# Nixie_Clock_ESP32_IN14.net
KiCad netlist of a schematic drawn in EAGLE
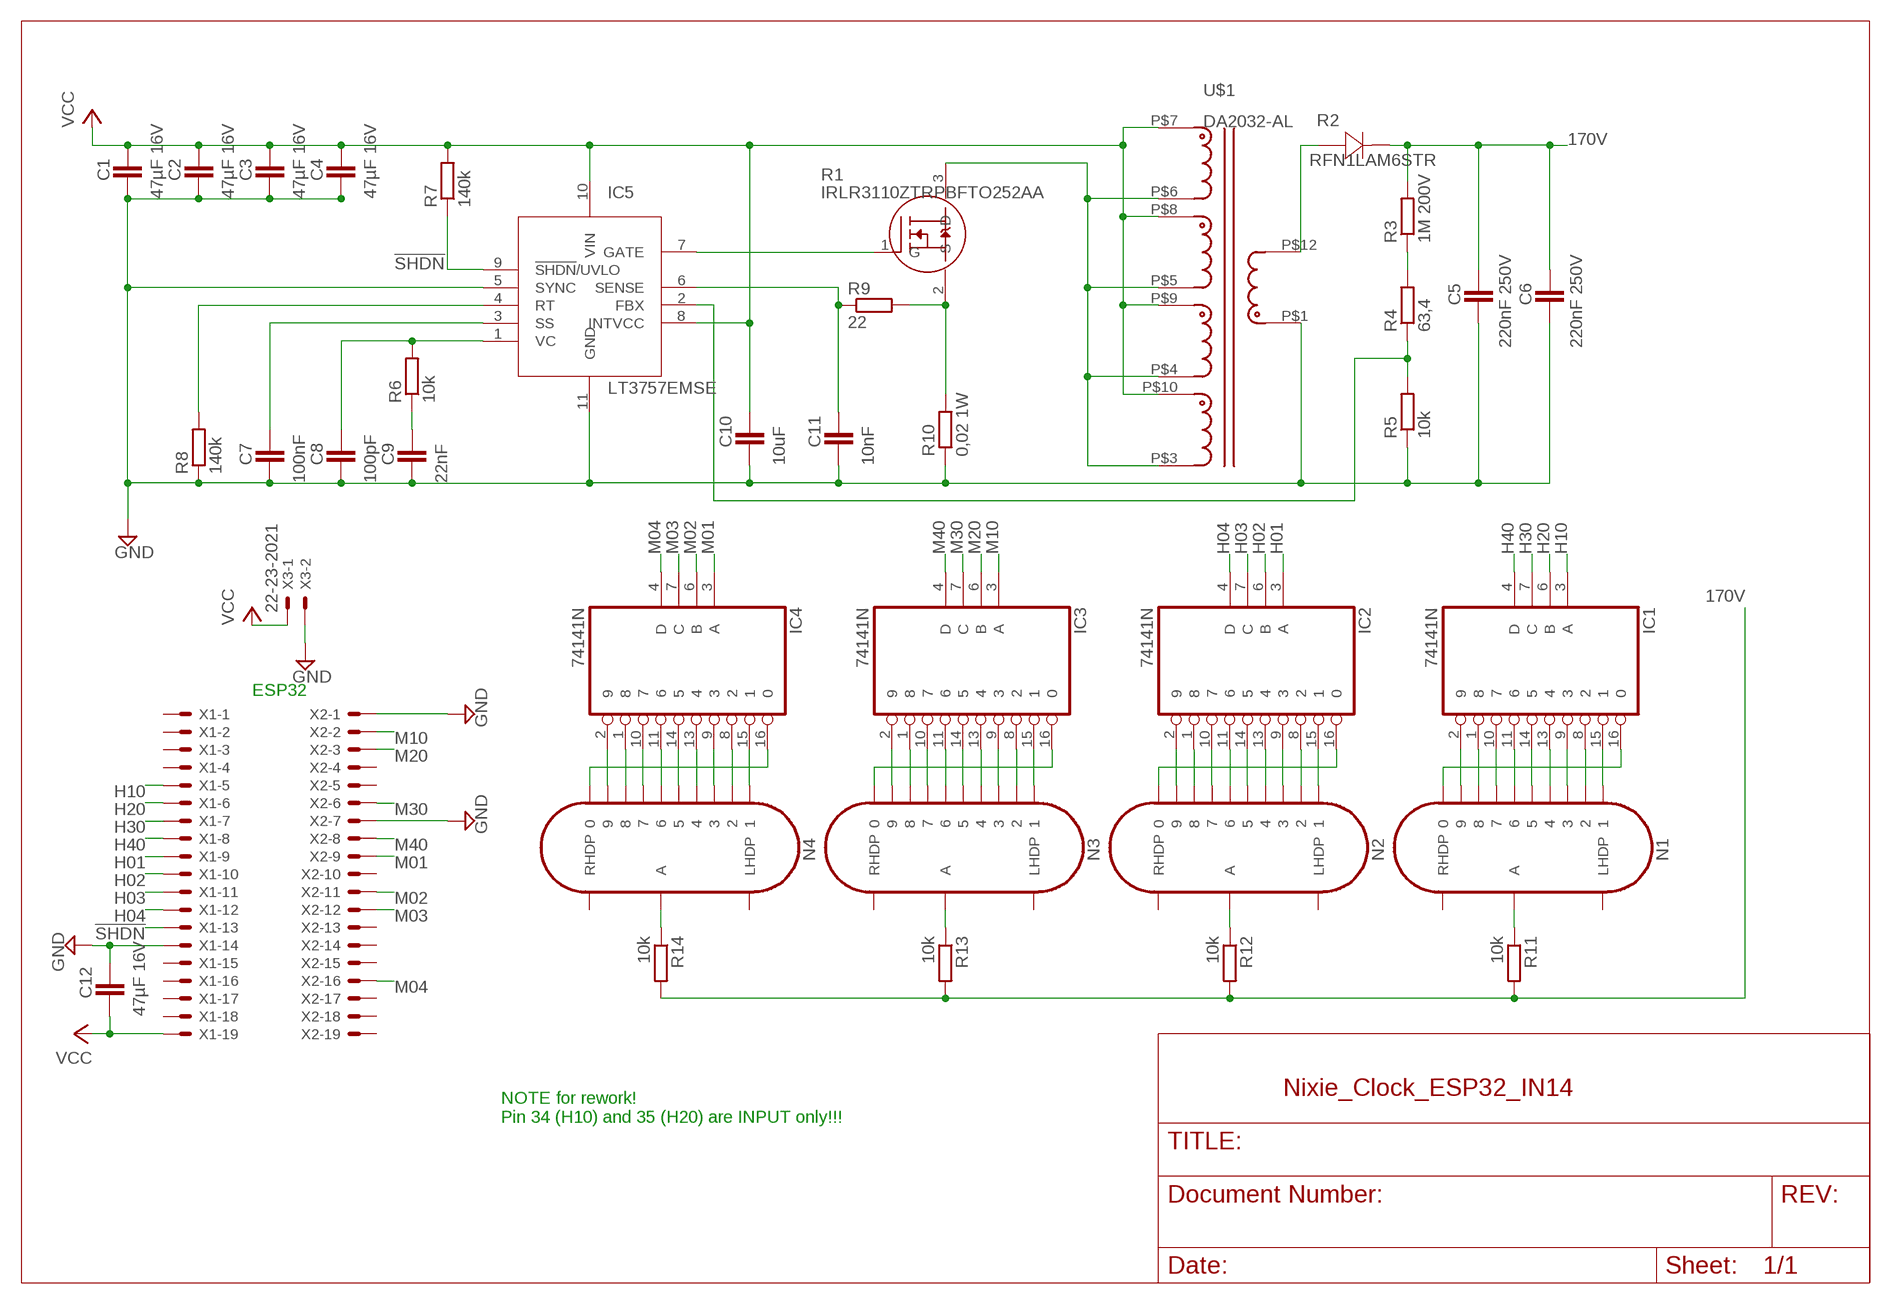
[diagram p0: schematic, sheet 1]

(export (version "E")
  (design (tool "Eeschema 10.0.6"))
  (components
    (comp (ref "C1")
      (value "47µF 16V")
      (footprint "eagle-import:C1210")
      (libsource (lib "eagle-import") (part "C-EUC1210"))
    )
    (comp (ref "C2")
      (value "47µF 16V")
      (footprint "eagle-import:C1210")
      (libsource (lib "eagle-import") (part "C-EUC1210"))
    )
    (comp (ref "C3")
      (value "47µF 16V")
      (footprint "eagle-import:C1210")
      (libsource (lib "eagle-import") (part "C-EUC1210"))
    )
    (comp (ref "C4")
      (value "47µF 16V")
      (footprint "eagle-import:C1210")
      (libsource (lib "eagle-import") (part "C-EUC1210"))
    )
    (comp (ref "C5")
      (value "220nF 250V")
      (footprint "eagle-import:C1206")
      (libsource (lib "eagle-import") (part "C-EUC1206"))
    )
    (comp (ref "C6")
      (value "220nF 250V")
      (footprint "eagle-import:C1206")
      (libsource (lib "eagle-import") (part "C-EUC1206"))
    )
    (comp (ref "C7")
      (value "100nF")
      (footprint "eagle-import:C0805")
      (libsource (lib "eagle-import") (part "C-EUC0805"))
    )
    (comp (ref "C8")
      (value "100pF")
      (footprint "eagle-import:C0805")
      (libsource (lib "eagle-import") (part "C-EUC0805"))
    )
    (comp (ref "C9")
      (value "22nF")
      (footprint "eagle-import:C0805")
      (libsource (lib "eagle-import") (part "C-EUC0805"))
    )
    (comp (ref "C10")
      (value "10uF")
      (footprint "eagle-import:C0805")
      (libsource (lib "eagle-import") (part "C-EUC0805"))
    )
    (comp (ref "C11")
      (value "10nF")
      (footprint "eagle-import:C0805")
      (libsource (lib "eagle-import") (part "C-EUC0805"))
    )
    (comp (ref "C12")
      (value "47µF 16V")
      (footprint "eagle-import:C1210")
      (libsource (lib "eagle-import") (part "C-EUC1210"))
    )
    (comp (ref "IC1")
      (value "74141N")
      (footprint "eagle-import:DIL16")
      (libsource (lib "eagle-import") (part "74141N"))
    )
    (comp (ref "IC2")
      (value "74141N")
      (footprint "eagle-import:DIL16")
      (libsource (lib "eagle-import") (part "74141N"))
    )
    (comp (ref "IC3")
      (value "74141N")
      (footprint "eagle-import:DIL16")
      (libsource (lib "eagle-import") (part "74141N"))
    )
    (comp (ref "IC4")
      (value "74141N")
      (footprint "eagle-import:DIL16")
      (libsource (lib "eagle-import") (part "74141N"))
    )
    (comp (ref "IC5")
      (value "LT3757EMSE")
      (footprint "eagle-import:MSOP10")
      (libsource (lib "eagle-import") (part "LT3757EMSE"))
    )
    (comp (ref "N1")
      (value "IN-14")
      (footprint "eagle-import:IN-14")
      (libsource (lib "eagle-import") (part "IN-14"))
    )
    (comp (ref "N2")
      (value "IN-14")
      (footprint "eagle-import:IN-14")
      (libsource (lib "eagle-import") (part "IN-14"))
    )
    (comp (ref "N3")
      (value "IN-14")
      (footprint "eagle-import:IN-14")
      (libsource (lib "eagle-import") (part "IN-14"))
    )
    (comp (ref "N4")
      (value "IN-14")
      (footprint "eagle-import:IN-14")
      (libsource (lib "eagle-import") (part "IN-14"))
    )
    (comp (ref "R1")
      (value "IRLR3110ZTRPBFTO252AA")
      (footprint "eagle-import:TO252")
      (libsource (lib "eagle-import") (part "IRLR3110ZTRPBFTO252AA"))
    )
    (comp (ref "R2")
      (value "RFN1LAM6STR")
      (footprint "eagle-import:DIO_RB050LAM_ROM")
      (fields (field (name "COPYRIGHT") "Copyright (C) 2018 Accelerated Designs. All rights reserved"))
      (libsource (lib "eagle-import") (part "RFN1LAM6STR"))
    )
    (comp (ref "R3")
      (value "1M 200V")
      (footprint "eagle-import:R0805")
      (libsource (lib "eagle-import") (part "R-EU_R0805"))
    )
    (comp (ref "R4")
      (value "63,4")
      (footprint "eagle-import:R0805")
      (libsource (lib "eagle-import") (part "R-EU_R0805"))
    )
    (comp (ref "R5")
      (value "10k")
      (footprint "eagle-import:R0805")
      (libsource (lib "eagle-import") (part "R-EU_R0805"))
    )
    (comp (ref "R6")
      (value "10k")
      (footprint "eagle-import:R0805")
      (libsource (lib "eagle-import") (part "R-EU_R0805"))
    )
    (comp (ref "R7")
      (value "140k")
      (footprint "eagle-import:R0805")
      (libsource (lib "eagle-import") (part "R-EU_R0805"))
    )
    (comp (ref "R8")
      (value "140k")
      (footprint "eagle-import:R0805")
      (libsource (lib "eagle-import") (part "R-EU_R0805"))
    )
    (comp (ref "R9")
      (value "22")
      (footprint "eagle-import:R1206")
      (libsource (lib "eagle-import") (part "R-EU_R1206"))
    )
    (comp (ref "R10")
      (value "0,02 1W")
      (footprint "eagle-import:R2010")
      (libsource (lib "eagle-import") (part "R-EU_R2010"))
    )
    (comp (ref "R11")
      (value "10k")
      (footprint "eagle-import:R0805")
      (libsource (lib "eagle-import") (part "R-EU_R0805"))
    )
    (comp (ref "R12")
      (value "10k")
      (footprint "eagle-import:R0805")
      (libsource (lib "eagle-import") (part "R-EU_R0805"))
    )
    (comp (ref "R13")
      (value "10k")
      (footprint "eagle-import:R0805")
      (libsource (lib "eagle-import") (part "R-EU_R0805"))
    )
    (comp (ref "R14")
      (value "10k")
      (footprint "eagle-import:R0805")
      (libsource (lib "eagle-import") (part "R-EU_R0805"))
    )
    (comp (ref "U$1")
      (value "DA2032-AL")
      (footprint "eagle-import:DA2032-AL")
      (libsource (lib "eagle-import") (part "DA2032-AL"))
    )
    (comp (ref "X1")
      (value "C-GRID-19-70543")
      (footprint "eagle-import:70543-19")
      (fields (field (name "MF") "MOLEX"))
      (libsource (lib "eagle-import") (part "C-GRID-19-70543"))
    )
    (comp (ref "X2")
      (value "C-GRID-19-70543")
      (footprint "eagle-import:70543-19")
      (fields (field (name "MF") "MOLEX"))
      (libsource (lib "eagle-import") (part "C-GRID-19-70543"))
    )
    (comp (ref "X3")
      (value "22-23-2021")
      (footprint "eagle-import:22-23-2021")
      (fields (field (name "MF") "MOLEX"))
      (libsource (lib "eagle-import") (part "22-23-2021"))
    )
  )
  (nets
    (net (code "1") (name "/170V") (class "Default")
      (node (ref "C5") (pin "1") (pinfunction "1_1") (pintype "passive"))
      (node (ref "C6") (pin "1") (pinfunction "1_1") (pintype "passive"))
      (node (ref "R11") (pin "2") (pinfunction "2_2") (pintype "passive"))
      (node (ref "R12") (pin "2") (pinfunction "2_2") (pintype "passive"))
      (node (ref "R13") (pin "2") (pinfunction "2_2") (pintype "passive"))
      (node (ref "R14") (pin "2") (pinfunction "2_2") (pintype "passive"))
      (node (ref "R2") (pin "1") (pinfunction "0_1") (pintype "passive"))
      (node (ref "R3") (pin "2") (pinfunction "2_2") (pintype "passive"))
    )
    (net (code "2") (name "/H01") (class "Default")
      (node (ref "IC2") (pin "3") (pinfunction "A_3") (pintype "input"))
      (node (ref "X1") (pin "9") (pinfunction "S_9") (pintype "passive"))
    )
    (net (code "3") (name "/H02") (class "Default")
      (node (ref "IC2") (pin "6") (pinfunction "B_6") (pintype "input"))
      (node (ref "X1") (pin "10") (pinfunction "S_10") (pintype "passive"))
    )
    (net (code "4") (name "/H03") (class "Default")
      (node (ref "IC2") (pin "7") (pinfunction "C_7") (pintype "input"))
      (node (ref "X1") (pin "11") (pinfunction "S_11") (pintype "passive"))
    )
    (net (code "5") (name "/H04") (class "Default")
      (node (ref "IC2") (pin "4") (pinfunction "D_4") (pintype "input"))
      (node (ref "X1") (pin "12") (pinfunction "S_12") (pintype "passive"))
    )
    (net (code "6") (name "/H10") (class "Default")
      (node (ref "IC1") (pin "3") (pinfunction "A_3") (pintype "input"))
      (node (ref "X1") (pin "5") (pinfunction "S_5") (pintype "passive"))
    )
    (net (code "7") (name "/H20") (class "Default")
      (node (ref "IC1") (pin "6") (pinfunction "B_6") (pintype "input"))
      (node (ref "X1") (pin "6") (pinfunction "S_6") (pintype "passive"))
    )
    (net (code "8") (name "/H30") (class "Default")
      (node (ref "IC1") (pin "7") (pinfunction "C_7") (pintype "input"))
      (node (ref "X1") (pin "7") (pinfunction "S_7") (pintype "passive"))
    )
    (net (code "9") (name "/H40") (class "Default")
      (node (ref "IC1") (pin "4") (pinfunction "D_4") (pintype "input"))
      (node (ref "X1") (pin "8") (pinfunction "S_8") (pintype "passive"))
    )
    (net (code "10") (name "/M01") (class "Default")
      (node (ref "IC4") (pin "3") (pinfunction "A_3") (pintype "input"))
      (node (ref "X2") (pin "9") (pinfunction "S_9") (pintype "passive"))
    )
    (net (code "11") (name "/M02") (class "Default")
      (node (ref "IC4") (pin "6") (pinfunction "B_6") (pintype "input"))
      (node (ref "X2") (pin "11") (pinfunction "S_11") (pintype "passive"))
    )
    (net (code "12") (name "/M03") (class "Default")
      (node (ref "IC4") (pin "7") (pinfunction "C_7") (pintype "input"))
      (node (ref "X2") (pin "12") (pinfunction "S_12") (pintype "passive"))
    )
    (net (code "13") (name "/M04") (class "Default")
      (node (ref "IC4") (pin "4") (pinfunction "D_4") (pintype "input"))
      (node (ref "X2") (pin "16") (pinfunction "S_16") (pintype "passive"))
    )
    (net (code "14") (name "/M10") (class "Default")
      (node (ref "IC3") (pin "3") (pinfunction "A_3") (pintype "input"))
      (node (ref "X2") (pin "2") (pinfunction "S_2") (pintype "passive"))
    )
    (net (code "15") (name "/M20") (class "Default")
      (node (ref "IC3") (pin "6") (pinfunction "B_6") (pintype "input"))
      (node (ref "X2") (pin "3") (pinfunction "S_3") (pintype "passive"))
    )
    (net (code "16") (name "/M30") (class "Default")
      (node (ref "IC3") (pin "7") (pinfunction "C_7") (pintype "input"))
      (node (ref "X2") (pin "6") (pinfunction "S_6") (pintype "passive"))
    )
    (net (code "17") (name "/M40") (class "Default")
      (node (ref "IC3") (pin "4") (pinfunction "D_4") (pintype "input"))
      (node (ref "X2") (pin "8") (pinfunction "S_8") (pintype "passive"))
    )
    (net (code "18") (name "/~{SHDN}") (class "Default")
      (node (ref "IC5") (pin "9") (pinfunction "~{SHDN}/UVLO_9") (pintype "bidirectional"))
      (node (ref "R7") (pin "1") (pinfunction "1_1") (pintype "passive"))
      (node (ref "X1") (pin "13") (pinfunction "S_13") (pintype "passive"))
    )
    (net (code "19") (name "GND") (class "Default")
      (node (ref "C1") (pin "2") (pinfunction "2_2") (pintype "passive"))
      (node (ref "C10") (pin "2") (pinfunction "2_2") (pintype "passive"))
      (node (ref "C11") (pin "2") (pinfunction "2_2") (pintype "passive"))
      (node (ref "C12") (pin "1") (pinfunction "1_1") (pintype "passive"))
      (node (ref "C2") (pin "2") (pinfunction "2_2") (pintype "passive"))
      (node (ref "C3") (pin "2") (pinfunction "2_2") (pintype "passive"))
      (node (ref "C4") (pin "2") (pinfunction "2_2") (pintype "passive"))
      (node (ref "C5") (pin "2") (pinfunction "2_2") (pintype "passive"))
      (node (ref "C6") (pin "2") (pinfunction "2_2") (pintype "passive"))
      (node (ref "C7") (pin "2") (pinfunction "2_2") (pintype "passive"))
      (node (ref "C8") (pin "2") (pinfunction "2_2") (pintype "passive"))
      (node (ref "C9") (pin "2") (pinfunction "2_2") (pintype "passive"))
      (node (ref "IC5") (pin "11") (pinfunction "GND_11") (pintype "bidirectional"))
      (node (ref "IC5") (pin "5") (pinfunction "SYNC_5") (pintype "bidirectional"))
      (node (ref "R10") (pin "1") (pinfunction "1_1") (pintype "passive"))
      (node (ref "R5") (pin "1") (pinfunction "1_1") (pintype "passive"))
      (node (ref "R8") (pin "1") (pinfunction "1_1") (pintype "passive"))
      (node (ref "U$1") (pin "P$1") (pinfunction "1_P$1") (pintype "passive"))
      (node (ref "X1") (pin "14") (pinfunction "S_14") (pintype "passive"))
      (node (ref "X2") (pin "1") (pinfunction "S_1") (pintype "passive"))
      (node (ref "X2") (pin "7") (pinfunction "S_7") (pintype "passive"))
      (node (ref "X3") (pin "2") (pinfunction "S_2") (pintype "passive"))
    )
    (net (code "20") (name "Net-(C9-Pad1)") (class "Default")
      (node (ref "C9") (pin "1") (pinfunction "1_1") (pintype "passive"))
      (node (ref "R6") (pin "1") (pinfunction "1_1") (pintype "passive"))
    )
    (net (code "21") (name "Net-(IC1A-0)") (class "Default")
      (node (ref "IC1") (pin "16") (pinfunction "0_16") (pintype "open_collector"))
      (node (ref "N1") (pin "0") (pinfunction "0_0") (pintype "bidirectional"))
    )
    (net (code "22") (name "Net-(IC1A-1)") (class "Default")
      (node (ref "IC1") (pin "15") (pinfunction "1_15") (pintype "open_collector"))
      (node (ref "N1") (pin "1") (pinfunction "1_1") (pintype "bidirectional"))
    )
    (net (code "23") (name "Net-(IC1A-2)") (class "Default")
      (node (ref "IC1") (pin "8") (pinfunction "2_8") (pintype "open_collector"))
      (node (ref "N1") (pin "2") (pinfunction "2_2") (pintype "bidirectional"))
    )
    (net (code "24") (name "Net-(IC1A-3)") (class "Default")
      (node (ref "IC1") (pin "9") (pinfunction "3_9") (pintype "open_collector"))
      (node (ref "N1") (pin "3") (pinfunction "3_3") (pintype "bidirectional"))
    )
    (net (code "25") (name "Net-(IC1A-4)") (class "Default")
      (node (ref "IC1") (pin "13") (pinfunction "4_13") (pintype "open_collector"))
      (node (ref "N1") (pin "4") (pinfunction "4_4") (pintype "bidirectional"))
    )
    (net (code "26") (name "Net-(IC1A-5)") (class "Default")
      (node (ref "IC1") (pin "14") (pinfunction "5_14") (pintype "open_collector"))
      (node (ref "N1") (pin "5") (pinfunction "5_5") (pintype "bidirectional"))
    )
    (net (code "27") (name "Net-(IC1A-6)") (class "Default")
      (node (ref "IC1") (pin "11") (pinfunction "6_11") (pintype "open_collector"))
      (node (ref "N1") (pin "6") (pinfunction "6_6") (pintype "bidirectional"))
    )
    (net (code "28") (name "Net-(IC1A-7)") (class "Default")
      (node (ref "IC1") (pin "10") (pinfunction "7_10") (pintype "open_collector"))
      (node (ref "N1") (pin "7") (pinfunction "7_7") (pintype "bidirectional"))
    )
    (net (code "29") (name "Net-(IC1A-8)") (class "Default")
      (node (ref "IC1") (pin "1") (pinfunction "8_1") (pintype "open_collector"))
      (node (ref "N1") (pin "8") (pinfunction "8_8") (pintype "bidirectional"))
    )
    (net (code "30") (name "Net-(IC1A-9)") (class "Default")
      (node (ref "IC1") (pin "2") (pinfunction "9_2") (pintype "open_collector"))
      (node (ref "N1") (pin "9") (pinfunction "9_9") (pintype "bidirectional"))
    )
    (net (code "31") (name "Net-(IC2A-0)") (class "Default")
      (node (ref "IC2") (pin "16") (pinfunction "0_16") (pintype "open_collector"))
      (node (ref "N2") (pin "0") (pinfunction "0_0") (pintype "bidirectional"))
    )
    (net (code "32") (name "Net-(IC2A-1)") (class "Default")
      (node (ref "IC2") (pin "15") (pinfunction "1_15") (pintype "open_collector"))
      (node (ref "N2") (pin "1") (pinfunction "1_1") (pintype "bidirectional"))
    )
    (net (code "33") (name "Net-(IC2A-2)") (class "Default")
      (node (ref "IC2") (pin "8") (pinfunction "2_8") (pintype "open_collector"))
      (node (ref "N2") (pin "2") (pinfunction "2_2") (pintype "bidirectional"))
    )
    (net (code "34") (name "Net-(IC2A-3)") (class "Default")
      (node (ref "IC2") (pin "9") (pinfunction "3_9") (pintype "open_collector"))
      (node (ref "N2") (pin "3") (pinfunction "3_3") (pintype "bidirectional"))
    )
    (net (code "35") (name "Net-(IC2A-4)") (class "Default")
      (node (ref "IC2") (pin "13") (pinfunction "4_13") (pintype "open_collector"))
      (node (ref "N2") (pin "4") (pinfunction "4_4") (pintype "bidirectional"))
    )
    (net (code "36") (name "Net-(IC2A-5)") (class "Default")
      (node (ref "IC2") (pin "14") (pinfunction "5_14") (pintype "open_collector"))
      (node (ref "N2") (pin "5") (pinfunction "5_5") (pintype "bidirectional"))
    )
    (net (code "37") (name "Net-(IC2A-6)") (class "Default")
      (node (ref "IC2") (pin "11") (pinfunction "6_11") (pintype "open_collector"))
      (node (ref "N2") (pin "6") (pinfunction "6_6") (pintype "bidirectional"))
    )
    (net (code "38") (name "Net-(IC2A-7)") (class "Default")
      (node (ref "IC2") (pin "10") (pinfunction "7_10") (pintype "open_collector"))
      (node (ref "N2") (pin "7") (pinfunction "7_7") (pintype "bidirectional"))
    )
    (net (code "39") (name "Net-(IC2A-8)") (class "Default")
      (node (ref "IC2") (pin "1") (pinfunction "8_1") (pintype "open_collector"))
      (node (ref "N2") (pin "8") (pinfunction "8_8") (pintype "bidirectional"))
    )
    (net (code "40") (name "Net-(IC2A-9)") (class "Default")
      (node (ref "IC2") (pin "2") (pinfunction "9_2") (pintype "open_collector"))
      (node (ref "N2") (pin "9") (pinfunction "9_9") (pintype "bidirectional"))
    )
    (net (code "41") (name "Net-(IC3A-0)") (class "Default")
      (node (ref "IC3") (pin "16") (pinfunction "0_16") (pintype "open_collector"))
      (node (ref "N3") (pin "0") (pinfunction "0_0") (pintype "bidirectional"))
    )
    (net (code "42") (name "Net-(IC3A-1)") (class "Default")
      (node (ref "IC3") (pin "15") (pinfunction "1_15") (pintype "open_collector"))
      (node (ref "N3") (pin "1") (pinfunction "1_1") (pintype "bidirectional"))
    )
    (net (code "43") (name "Net-(IC3A-2)") (class "Default")
      (node (ref "IC3") (pin "8") (pinfunction "2_8") (pintype "open_collector"))
      (node (ref "N3") (pin "2") (pinfunction "2_2") (pintype "bidirectional"))
    )
    (net (code "44") (name "Net-(IC3A-3)") (class "Default")
      (node (ref "IC3") (pin "9") (pinfunction "3_9") (pintype "open_collector"))
      (node (ref "N3") (pin "3") (pinfunction "3_3") (pintype "bidirectional"))
    )
    (net (code "45") (name "Net-(IC3A-4)") (class "Default")
      (node (ref "IC3") (pin "13") (pinfunction "4_13") (pintype "open_collector"))
      (node (ref "N3") (pin "4") (pinfunction "4_4") (pintype "bidirectional"))
    )
    (net (code "46") (name "Net-(IC3A-5)") (class "Default")
      (node (ref "IC3") (pin "14") (pinfunction "5_14") (pintype "open_collector"))
      (node (ref "N3") (pin "5") (pinfunction "5_5") (pintype "bidirectional"))
    )
    (net (code "47") (name "Net-(IC3A-6)") (class "Default")
      (node (ref "IC3") (pin "11") (pinfunction "6_11") (pintype "open_collector"))
      (node (ref "N3") (pin "6") (pinfunction "6_6") (pintype "bidirectional"))
    )
    (net (code "48") (name "Net-(IC3A-7)") (class "Default")
      (node (ref "IC3") (pin "10") (pinfunction "7_10") (pintype "open_collector"))
      (node (ref "N3") (pin "7") (pinfunction "7_7") (pintype "bidirectional"))
    )
    (net (code "49") (name "Net-(IC3A-8)") (class "Default")
      (node (ref "IC3") (pin "1") (pinfunction "8_1") (pintype "open_collector"))
      (node (ref "N3") (pin "8") (pinfunction "8_8") (pintype "bidirectional"))
    )
    (net (code "50") (name "Net-(IC3A-9)") (class "Default")
      (node (ref "IC3") (pin "2") (pinfunction "9_2") (pintype "open_collector"))
      (node (ref "N3") (pin "9") (pinfunction "9_9") (pintype "bidirectional"))
    )
    (net (code "51") (name "Net-(IC4A-0)") (class "Default")
      (node (ref "IC4") (pin "16") (pinfunction "0_16") (pintype "open_collector"))
      (node (ref "N4") (pin "0") (pinfunction "0_0") (pintype "bidirectional"))
    )
    (net (code "52") (name "Net-(IC4A-1)") (class "Default")
      (node (ref "IC4") (pin "15") (pinfunction "1_15") (pintype "open_collector"))
      (node (ref "N4") (pin "1") (pinfunction "1_1") (pintype "bidirectional"))
    )
    (net (code "53") (name "Net-(IC4A-2)") (class "Default")
      (node (ref "IC4") (pin "8") (pinfunction "2_8") (pintype "open_collector"))
      (node (ref "N4") (pin "2") (pinfunction "2_2") (pintype "bidirectional"))
    )
    (net (code "54") (name "Net-(IC4A-3)") (class "Default")
      (node (ref "IC4") (pin "9") (pinfunction "3_9") (pintype "open_collector"))
      (node (ref "N4") (pin "3") (pinfunction "3_3") (pintype "bidirectional"))
    )
    (net (code "55") (name "Net-(IC4A-4)") (class "Default")
      (node (ref "IC4") (pin "13") (pinfunction "4_13") (pintype "open_collector"))
      (node (ref "N4") (pin "4") (pinfunction "4_4") (pintype "bidirectional"))
    )
    (net (code "56") (name "Net-(IC4A-5)") (class "Default")
      (node (ref "IC4") (pin "14") (pinfunction "5_14") (pintype "open_collector"))
      (node (ref "N4") (pin "5") (pinfunction "5_5") (pintype "bidirectional"))
    )
    (net (code "57") (name "Net-(IC4A-6)") (class "Default")
      (node (ref "IC4") (pin "11") (pinfunction "6_11") (pintype "open_collector"))
      (node (ref "N4") (pin "6") (pinfunction "6_6") (pintype "bidirectional"))
    )
    (net (code "58") (name "Net-(IC4A-7)") (class "Default")
      (node (ref "IC4") (pin "10") (pinfunction "7_10") (pintype "open_collector"))
      (node (ref "N4") (pin "7") (pinfunction "7_7") (pintype "bidirectional"))
    )
    (net (code "59") (name "Net-(IC4A-8)") (class "Default")
      (node (ref "IC4") (pin "1") (pinfunction "8_1") (pintype "open_collector"))
      (node (ref "N4") (pin "8") (pinfunction "8_8") (pintype "bidirectional"))
    )
    (net (code "60") (name "Net-(IC4A-9)") (class "Default")
      (node (ref "IC4") (pin "2") (pinfunction "9_2") (pintype "open_collector"))
      (node (ref "N4") (pin "9") (pinfunction "9_9") (pintype "bidirectional"))
    )
    (net (code "61") (name "Net-(IC5-FBX)") (class "Default")
      (node (ref "IC5") (pin "2") (pinfunction "FBX_2") (pintype "bidirectional"))
      (node (ref "R4") (pin "1") (pinfunction "1_1") (pintype "passive"))
      (node (ref "R5") (pin "2") (pinfunction "2_2") (pintype "passive"))
    )
    (net (code "62") (name "Net-(IC5-GATE)") (class "Default")
      (node (ref "IC5") (pin "7") (pinfunction "GATE_7") (pintype "bidirectional"))
      (node (ref "R1") (pin "1") (pinfunction "G_1") (pintype "bidirectional"))
    )
    (net (code "63") (name "Net-(IC5-RT)") (class "Default")
      (node (ref "IC5") (pin "4") (pinfunction "RT_4") (pintype "bidirectional"))
      (node (ref "R8") (pin "2") (pinfunction "2_2") (pintype "passive"))
    )
    (net (code "64") (name "Net-(IC5-SENSE)") (class "Default")
      (node (ref "C11") (pin "1") (pinfunction "1_1") (pintype "passive"))
      (node (ref "IC5") (pin "6") (pinfunction "SENSE_6") (pintype "bidirectional"))
      (node (ref "R9") (pin "1") (pinfunction "1_1") (pintype "passive"))
    )
    (net (code "65") (name "Net-(IC5-SS)") (class "Default")
      (node (ref "C7") (pin "1") (pinfunction "1_1") (pintype "passive"))
      (node (ref "IC5") (pin "3") (pinfunction "SS_3") (pintype "bidirectional"))
    )
    (net (code "66") (name "Net-(IC5-VC)") (class "Default")
      (node (ref "C8") (pin "1") (pinfunction "1_1") (pintype "passive"))
      (node (ref "IC5") (pin "1") (pinfunction "VC_1") (pintype "bidirectional"))
      (node (ref "R6") (pin "2") (pinfunction "2_2") (pintype "passive"))
    )
    (net (code "67") (name "Net-(N1-PadA)") (class "Default")
      (node (ref "N1") (pin "A") (pinfunction "A_A") (pintype "bidirectional"))
      (node (ref "R11") (pin "1") (pinfunction "1_1") (pintype "passive"))
    )
    (net (code "68") (name "Net-(N2-PadA)") (class "Default")
      (node (ref "N2") (pin "A") (pinfunction "A_A") (pintype "bidirectional"))
      (node (ref "R12") (pin "1") (pinfunction "1_1") (pintype "passive"))
    )
    (net (code "69") (name "Net-(N3-PadA)") (class "Default")
      (node (ref "N3") (pin "A") (pinfunction "A_A") (pintype "bidirectional"))
      (node (ref "R13") (pin "1") (pinfunction "1_1") (pintype "passive"))
    )
    (net (code "70") (name "Net-(N4-PadA)") (class "Default")
      (node (ref "N4") (pin "A") (pinfunction "A_A") (pintype "bidirectional"))
      (node (ref "R14") (pin "1") (pinfunction "1_1") (pintype "passive"))
    )
    (net (code "71") (name "Net-(R1-D)") (class "Default")
      (node (ref "R1") (pin "3") (pinfunction "D_3") (pintype "bidirectional"))
      (node (ref "U$1") (pin "P$3") (pinfunction "3_P$3") (pintype "passive"))
      (node (ref "U$1") (pin "P$4") (pinfunction "4_P$4") (pintype "passive"))
      (node (ref "U$1") (pin "P$5") (pinfunction "5_P$5") (pintype "passive"))
      (node (ref "U$1") (pin "P$6") (pinfunction "6_P$6") (pintype "passive"))
    )
    (net (code "72") (name "Net-(R1-S)") (class "Default")
      (node (ref "R1") (pin "2") (pinfunction "S_2") (pintype "bidirectional"))
      (node (ref "R10") (pin "2") (pinfunction "2_2") (pintype "passive"))
      (node (ref "R9") (pin "2") (pinfunction "2_2") (pintype "passive"))
    )
    (net (code "73") (name "Net-(R2-1)") (class "Default")
      (node (ref "R2") (pin "2") (pinfunction "1_2") (pintype "passive"))
      (node (ref "U$1") (pin "P$12") (pinfunction "12_P$12") (pintype "passive"))
    )
    (net (code "74") (name "Net-(R3-Pad1)") (class "Default")
      (node (ref "R3") (pin "1") (pinfunction "1_1") (pintype "passive"))
      (node (ref "R4") (pin "2") (pinfunction "2_2") (pintype "passive"))
    )
    (net (code "75") (name "VCC") (class "Default")
      (node (ref "C1") (pin "1") (pinfunction "1_1") (pintype "passive"))
      (node (ref "C10") (pin "1") (pinfunction "1_1") (pintype "passive"))
      (node (ref "C12") (pin "2") (pinfunction "2_2") (pintype "passive"))
      (node (ref "C2") (pin "1") (pinfunction "1_1") (pintype "passive"))
      (node (ref "C3") (pin "1") (pinfunction "1_1") (pintype "passive"))
      (node (ref "C4") (pin "1") (pinfunction "1_1") (pintype "passive"))
      (node (ref "IC5") (pin "10") (pinfunction "VIN_10") (pintype "power_in"))
      (node (ref "IC5") (pin "8") (pinfunction "INTVCC_8") (pintype "bidirectional"))
      (node (ref "R7") (pin "2") (pinfunction "2_2") (pintype "passive"))
      (node (ref "U$1") (pin "P$10") (pinfunction "10_P$10") (pintype "passive"))
      (node (ref "U$1") (pin "P$7") (pinfunction "7_P$7") (pintype "passive"))
      (node (ref "U$1") (pin "P$8") (pinfunction "8_P$8") (pintype "passive"))
      (node (ref "U$1") (pin "P$9") (pinfunction "9_P$9") (pintype "passive"))
      (node (ref "X1") (pin "19") (pinfunction "S_19") (pintype "passive"))
      (node (ref "X3") (pin "1") (pinfunction "S_1") (pintype "passive"))
    )
    (net (code "76") (name "unconnected-(N1-PadLHDP)") (class "Default")
      (node (ref "N1") (pin "LHDP") (pinfunction "LHDP_LHDP") (pintype "bidirectional"))
    )
    (net (code "77") (name "unconnected-(N1-PadRHDP)") (class "Default")
      (node (ref "N1") (pin "RHDP") (pinfunction "RHDP_RHDP") (pintype "bidirectional"))
    )
    (net (code "78") (name "unconnected-(N2-PadLHDP)") (class "Default")
      (node (ref "N2") (pin "LHDP") (pinfunction "LHDP_LHDP") (pintype "bidirectional"))
    )
    (net (code "79") (name "unconnected-(N2-PadRHDP)") (class "Default")
      (node (ref "N2") (pin "RHDP") (pinfunction "RHDP_RHDP") (pintype "bidirectional"))
    )
    (net (code "80") (name "unconnected-(N3-PadLHDP)") (class "Default")
      (node (ref "N3") (pin "LHDP") (pinfunction "LHDP_LHDP") (pintype "bidirectional"))
    )
    (net (code "81") (name "unconnected-(N3-PadRHDP)") (class "Default")
      (node (ref "N3") (pin "RHDP") (pinfunction "RHDP_RHDP") (pintype "bidirectional"))
    )
    (net (code "82") (name "unconnected-(N4-PadLHDP)") (class "Default")
      (node (ref "N4") (pin "LHDP") (pinfunction "LHDP_LHDP") (pintype "bidirectional"))
    )
    (net (code "83") (name "unconnected-(N4-PadRHDP)") (class "Default")
      (node (ref "N4") (pin "RHDP") (pinfunction "RHDP_RHDP") (pintype "bidirectional"))
    )
    (net (code "84") (name "unconnected-(X1A-S-Pad1)") (class "Default")
      (node (ref "X1") (pin "1") (pinfunction "S_1") (pintype "passive"))
    )
    (net (code "85") (name "unconnected-(X1G-S-Pad15)") (class "Default")
      (node (ref "X1") (pin "15") (pinfunction "S_15") (pintype "passive"))
    )
    (net (code "86") (name "unconnected-(X1H-S-Pad16)") (class "Default")
      (node (ref "X1") (pin "16") (pinfunction "S_16") (pintype "passive"))
    )
    (net (code "87") (name "unconnected-(X1I-S-Pad17)") (class "Default")
      (node (ref "X1") (pin "17") (pinfunction "S_17") (pintype "passive"))
    )
    (net (code "88") (name "unconnected-(X1J-S-Pad18)") (class "Default")
      (node (ref "X1") (pin "18") (pinfunction "S_18") (pintype "passive"))
    )
    (net (code "89") (name "unconnected-(X1L-S-Pad2)") (class "Default")
      (node (ref "X1") (pin "2") (pinfunction "S_2") (pintype "passive"))
    )
    (net (code "90") (name "unconnected-(X1M-S-Pad3)") (class "Default")
      (node (ref "X1") (pin "3") (pinfunction "S_3") (pintype "passive"))
    )
    (net (code "91") (name "unconnected-(X1N-S-Pad4)") (class "Default")
      (node (ref "X1") (pin "4") (pinfunction "S_4") (pintype "passive"))
    )
    (net (code "92") (name "unconnected-(X2B-S-Pad10)") (class "Default")
      (node (ref "X2") (pin "10") (pinfunction "S_10") (pintype "passive"))
    )
    (net (code "93") (name "unconnected-(X2E-S-Pad13)") (class "Default")
      (node (ref "X2") (pin "13") (pinfunction "S_13") (pintype "passive"))
    )
    (net (code "94") (name "unconnected-(X2F-S-Pad14)") (class "Default")
      (node (ref "X2") (pin "14") (pinfunction "S_14") (pintype "passive"))
    )
    (net (code "95") (name "unconnected-(X2G-S-Pad15)") (class "Default")
      (node (ref "X2") (pin "15") (pinfunction "S_15") (pintype "passive"))
    )
    (net (code "96") (name "unconnected-(X2I-S-Pad17)") (class "Default")
      (node (ref "X2") (pin "17") (pinfunction "S_17") (pintype "passive"))
    )
    (net (code "97") (name "unconnected-(X2J-S-Pad18)") (class "Default")
      (node (ref "X2") (pin "18") (pinfunction "S_18") (pintype "passive"))
    )
    (net (code "98") (name "unconnected-(X2K-S-Pad19)") (class "Default")
      (node (ref "X2") (pin "19") (pinfunction "S_19") (pintype "passive"))
    )
    (net (code "99") (name "unconnected-(X2N-S-Pad4)") (class "Default")
      (node (ref "X2") (pin "4") (pinfunction "S_4") (pintype "passive"))
    )
    (net (code "100") (name "unconnected-(X2O-S-Pad5)") (class "Default")
      (node (ref "X2") (pin "5") (pinfunction "S_5") (pintype "passive"))
    )
  )
)
